# Heater_element.net
KiCad netlist of a schematic drawn in Altium Designer
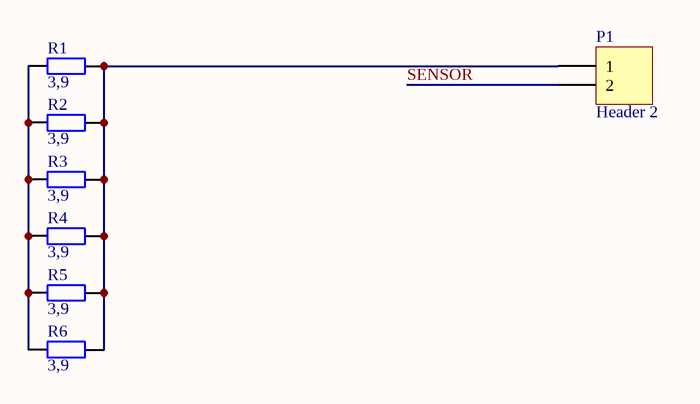
[diagram p0: Heater_element.SchDoc]

(export (version "E")
  (design (tool "Eeschema 10.0.6"))
  (components
    (comp (ref "P1")
      (value "Header 2")
      (footprint "HDR1X2")
      (description "Header, 2-Pin")
      (fields (field (name "PUBLISHER") "Altium Limited"))
      (libsource (lib "Miscellaneous Connectors") (part "Header 2"))
    )
    (comp (ref "R1")
      (value "3,9")
      (footprint "R2512")
      (description "Resistor")
      (fields (field (name "Comment") "WF25P3R9JTL WALSIN") (field (name "PUBLISHER") "Altium Limited"))
      (libsource (lib "Miscellaneous Devices") (part "Res2"))
    )
    (comp (ref "R2")
      (value "3,9")
      (footprint "R2512")
      (description "Resistor")
      (fields (field (name "Comment") "WF25P3R9JTL WALSIN") (field (name "PUBLISHER") "Altium Limited"))
      (libsource (lib "Miscellaneous Devices") (part "Res2"))
    )
    (comp (ref "R3")
      (value "3,9")
      (footprint "R2512")
      (description "Resistor")
      (fields (field (name "Comment") "WF25P3R9JTL WALSIN") (field (name "PUBLISHER") "Altium Limited"))
      (libsource (lib "Miscellaneous Devices") (part "Res2"))
    )
    (comp (ref "R4")
      (value "3,9")
      (footprint "R2512")
      (description "Resistor")
      (fields (field (name "Comment") "WF25P3R9JTL WALSIN") (field (name "PUBLISHER") "Altium Limited"))
      (libsource (lib "Miscellaneous Devices") (part "Res2"))
    )
    (comp (ref "R5")
      (value "3,9")
      (footprint "R2512")
      (description "Resistor")
      (fields (field (name "Comment") "WF25P3R9JTL WALSIN") (field (name "PUBLISHER") "Altium Limited"))
      (libsource (lib "Miscellaneous Devices") (part "Res2"))
    )
    (comp (ref "R6")
      (value "3,9")
      (footprint "R2512")
      (description "Resistor")
      (fields (field (name "Comment") "WF25P3R9JTL WALSIN") (field (name "PUBLISHER") "Altium Limited"))
      (libsource (lib "Miscellaneous Devices") (part "Res2"))
    )
  )
  (nets
    (net (code "1") (name "/SENSOR") (class "Default")
      (node (ref "P1") (pin "2") (pinfunction "2_2") (pintype "passive"))
    )
    (net (code "2") (name "Net-(P1-Pad1)") (class "Default")
      (node (ref "P1") (pin "1") (pinfunction "1_1") (pintype "passive"))
      (node (ref "R1") (pin "2") (pinfunction "2_2") (pintype "passive"))
      (node (ref "R2") (pin "2") (pinfunction "2_2") (pintype "passive"))
      (node (ref "R3") (pin "2") (pinfunction "2_2") (pintype "passive"))
      (node (ref "R4") (pin "2") (pinfunction "2_2") (pintype "passive"))
      (node (ref "R5") (pin "2") (pinfunction "2_2") (pintype "passive"))
      (node (ref "R6") (pin "2") (pinfunction "2_2") (pintype "passive"))
    )
    (net (code "3") (name "Net-(R1-Pad1)") (class "Default")
      (node (ref "R1") (pin "1") (pinfunction "1_1") (pintype "passive"))
      (node (ref "R2") (pin "1") (pinfunction "1_1") (pintype "passive"))
      (node (ref "R3") (pin "1") (pinfunction "1_1") (pintype "passive"))
      (node (ref "R4") (pin "1") (pinfunction "1_1") (pintype "passive"))
      (node (ref "R5") (pin "1") (pinfunction "1_1") (pintype "passive"))
      (node (ref "R6") (pin "1") (pinfunction "1_1") (pintype "passive"))
    )
  )
)
